# STLINK_V3EC.net
KiCad netlist of a schematic drawn in Altium Designer
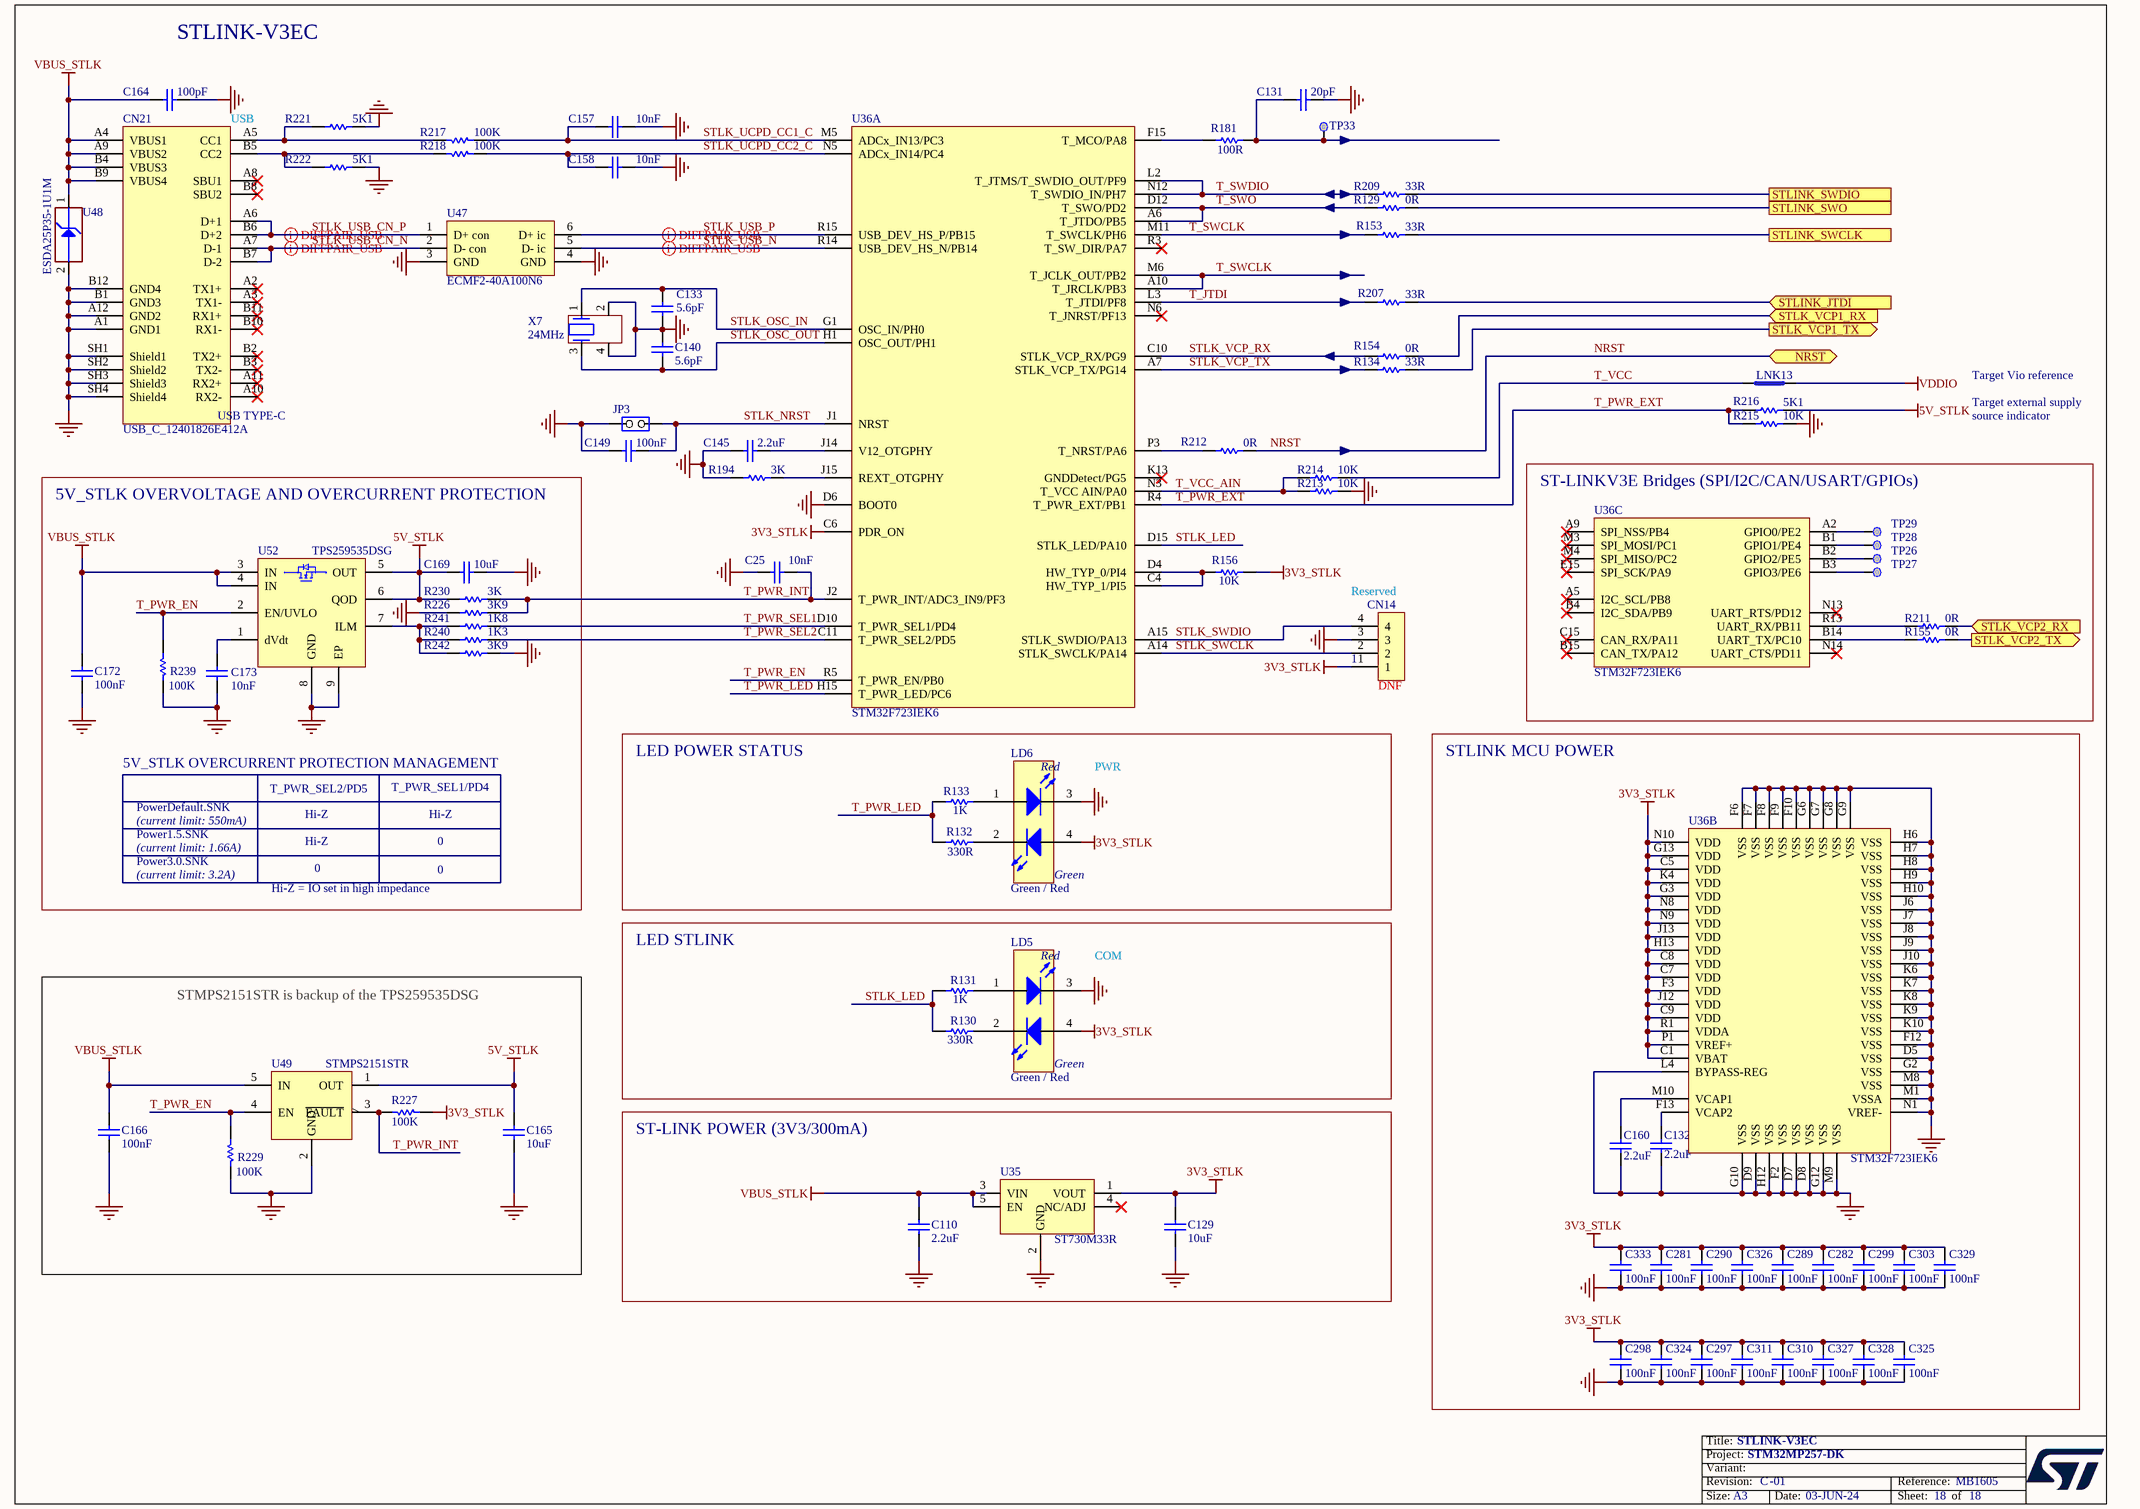
[diagram p0: STLINK_V3EC.SchDoc]

(export (version "E")
  (design (tool "Eeschema 10.0.6"))
  (components
    (comp (ref "C25")
      (value "10nF")
      (footprint "C0402")
      (description "Capacitor, MLCC, 10nF, 50V, X7R, +/-10%, 0402, T=0.5mm")
      (fields (field (name "INTERNAL_PART_NUMBER") "MCD-02198") (field (name "MANUFACTURER") "YAGEO"))
      (libsource (lib "MCD_PARTS_database") (part "Capacitor"))
    )
    (comp (ref "C110")
      (value "2.2uF")
      (footprint "C0805")
      (description "Capacitor, MLCC, 2.2uF, 25V, X7R, +/-10%, 0805, T=1,25mm")
      (fields
        (field (name "INTERNAL_PART_NUMBER") "MCD-02372")
        (field (name "MANUFACTURER_PART_NUMBER") "GRM21BR71E225KE11L")
      )
      (libsource (lib "MCD_PARTS_database") (part "Capacitor"))
    )
    (comp (ref "C129")
      (value "10uF")
      (footprint "C0603")
      (description "Capacitor, MLCC, 10uF, 10V, X5R, +/-10%, 0603, T=0.8mm")
      (fields (field (name "INTERNAL_PART_NUMBER") "MCD-00099") (field (name "MANUFACTURER") "MURATA"))
      (libsource (lib "MCD_PARTS_database") (part "Capacitor"))
    )
    (comp (ref "C131")
      (value "20pF")
      (footprint "C0402")
      (description "Capacitor, MLCC, 20pF, 50V, NPO, +/- 5%, 0402, T=0.5mm")
      (fields
        (field (name "INTERNAL_PART_NUMBER") "MCD-00016")
        (field (name "MANUFACTURER_PART_NUMBER") "CC0402JRNPO9BN200")
      )
      (libsource (lib "MCD_PARTS_database") (part "Capacitor"))
    )
    (comp (ref "C132")
      (value "2.2uF")
      (footprint "C0402")
      (description "Capacitor, MLCC, 2.2uF, 6.3V, X5R, +/-10%, 0402, T=0.5mm")
      (fields (field (name "INTERNAL_PART_NUMBER") "MCD-02606") (field (name "MANUFACTURER") "YAGEO"))
      (libsource (lib "MCD_PARTS_database") (part "Capacitor"))
    )
    (comp (ref "C133")
      (value "5.6pF")
      (footprint "C0402")
      (description "Capacitor, MLCC, 5.6pF, 50V, NPO, +/-0.1pF, 0402, T=0.5mm")
      (fields (field (name "INTERNAL_PART_NUMBER") "MCD-01374") (field (name "MANUFACTURER") "YAGEO"))
      (libsource (lib "MCD_PARTS_database") (part "Capacitor"))
    )
    (comp (ref "C140")
      (value "5.6pF")
      (footprint "C0402")
      (description "Capacitor, MLCC, 5.6pF, 50V, NPO, +/-0.1pF, 0402, T=0.5mm")
      (fields (field (name "INTERNAL_PART_NUMBER") "MCD-01374") (field (name "MANUFACTURER") "YAGEO"))
      (libsource (lib "MCD_PARTS_database") (part "Capacitor"))
    )
    (comp (ref "C145")
      (value "2.2uF")
      (footprint "C0402")
      (description "Capacitor, MLCC, 2.2uF, 6.3V, X5R, +/-10%, 0402, T=0.5mm")
      (fields (field (name "INTERNAL_PART_NUMBER") "MCD-02606") (field (name "MANUFACTURER") "YAGEO"))
      (libsource (lib "MCD_PARTS_database") (part "Capacitor"))
    )
    (comp (ref "C149")
      (value "100nF")
      (footprint "C0402")
      (description "Capacitor, MLCC, 100nF, 16V, X7R, +/-10%, 0402, T=0.5mm")
      (fields
        (field (name "INTERNAL_PART_NUMBER") "MCD-00006")
        (field (name "MANUFACTURER_PART_NUMBER") "CC0402KRX7R7BB104")
      )
      (libsource (lib "MCD_PARTS_database") (part "Capacitor"))
    )
    (comp (ref "C157")
      (value "10nF")
      (footprint "C0402")
      (description "Capacitor, MLCC, 10nF, 50V, X7R, +/-10%, 0402, T=0.5mm")
      (fields (field (name "INTERNAL_PART_NUMBER") "MCD-02198") (field (name "MANUFACTURER") "YAGEO"))
      (libsource (lib "MCD_PARTS_database") (part "Capacitor"))
    )
    (comp (ref "C158")
      (value "10nF")
      (footprint "C0402")
      (description "Capacitor, MLCC, 10nF, 50V, X7R, +/-10%, 0402, T=0.5mm")
      (fields (field (name "INTERNAL_PART_NUMBER") "MCD-02198") (field (name "MANUFACTURER") "YAGEO"))
      (libsource (lib "MCD_PARTS_database") (part "Capacitor"))
    )
    (comp (ref "C160")
      (value "2.2uF")
      (footprint "C0402")
      (description "Capacitor, MLCC, 2.2uF, 6.3V, X5R, +/-10%, 0402, T=0.5mm")
      (fields (field (name "INTERNAL_PART_NUMBER") "MCD-02606") (field (name "MANUFACTURER") "YAGEO"))
      (libsource (lib "MCD_PARTS_database") (part "Capacitor"))
    )
    (comp (ref "C164")
      (value "100pF")
      (footprint "C0402")
      (description "Capacitor, MLCC, 100pF, 50V, NPO, +/-5%, 0402, T=0.5mm")
      (fields (field (name "INTERNAL_PART_NUMBER") "MCD-00205") (field (name "MANUFACTURER") "YAGEO"))
      (libsource (lib "MCD_PARTS_database") (part "Capacitor"))
    )
    (comp (ref "C165")
      (value "10uF")
      (footprint "C0603")
      (description "Capacitor, MLCC, 10uF, 10V, X5R, +/-10%, 0603, T=0.8mm")
      (fields (field (name "INTERNAL_PART_NUMBER") "MCD-00099") (field (name "MANUFACTURER") "MURATA"))
      (libsource (lib "MCD_PARTS_database") (part "Capacitor"))
    )
    (comp (ref "C166")
      (value "100nF")
      (footprint "C0402")
      (description "Capacitor, MLCC, 100nF, 25V, X7R, +/-10%, 0402, T=0.5mm")
      (fields (field (name "INTERNAL_PART_NUMBER") "MCD-02355") (field (name "MANUFACTURER") "WALSIN"))
      (libsource (lib "MCD_PARTS_database") (part "Capacitor"))
    )
    (comp (ref "C169")
      (value "10uF")
      (footprint "C0603")
      (description "Capacitor, MLCC, 10uF, 10V, X5R, +/-10%, 0603, T=0.8mm")
      (fields (field (name "INTERNAL_PART_NUMBER") "MCD-00099") (field (name "MANUFACTURER") "MURATA"))
      (libsource (lib "MCD_PARTS_database") (part "Capacitor"))
    )
    (comp (ref "C172")
      (value "100nF")
      (footprint "C0402")
      (description "Capacitor, MLCC, 100nF, 25V, X7R, +/-10%, 0402, T=0.5mm")
      (fields (field (name "INTERNAL_PART_NUMBER") "MCD-02355") (field (name "MANUFACTURER") "WALSIN"))
      (libsource (lib "MCD_PARTS_database") (part "Capacitor"))
    )
    (comp (ref "C173")
      (value "10nF")
      (footprint "C0402")
      (description "Capacitor, MLCC, 10nF, 50V, X7R, +/-10%, 0402, T=0.5mm")
      (fields (field (name "INTERNAL_PART_NUMBER") "MCD-02198") (field (name "MANUFACTURER") "YAGEO"))
      (libsource (lib "MCD_PARTS_database") (part "Capacitor"))
    )
    (comp (ref "C281")
      (value "100nF")
      (footprint "C0402")
      (description "Capacitor, MLCC, 100nF, 16V, X7R, +/-10%, 0402, T=0.5mm")
      (fields
        (field (name "INTERNAL_PART_NUMBER") "MCD-00006")
        (field (name "MANUFACTURER_PART_NUMBER") "CC0402KRX7R7BB104")
      )
      (libsource (lib "MCD_PARTS_database") (part "Capacitor"))
    )
    (comp (ref "C282")
      (value "100nF")
      (footprint "C0402")
      (description "Capacitor, MLCC, 100nF, 16V, X7R, +/-10%, 0402, T=0.5mm")
      (fields
        (field (name "INTERNAL_PART_NUMBER") "MCD-00006")
        (field (name "MANUFACTURER_PART_NUMBER") "CC0402KRX7R7BB104")
      )
      (libsource (lib "MCD_PARTS_database") (part "Capacitor"))
    )
    (comp (ref "C289")
      (value "100nF")
      (footprint "C0402")
      (description "Capacitor, MLCC, 100nF, 16V, X7R, +/-10%, 0402, T=0.5mm")
      (fields
        (field (name "INTERNAL_PART_NUMBER") "MCD-00006")
        (field (name "MANUFACTURER_PART_NUMBER") "CC0402KRX7R7BB104")
      )
      (libsource (lib "MCD_PARTS_database") (part "Capacitor"))
    )
    (comp (ref "C290")
      (value "100nF")
      (footprint "C0402")
      (description "Capacitor, MLCC, 100nF, 16V, X7R, +/-10%, 0402, T=0.5mm")
      (fields
        (field (name "INTERNAL_PART_NUMBER") "MCD-00006")
        (field (name "MANUFACTURER_PART_NUMBER") "CC0402KRX7R7BB104")
      )
      (libsource (lib "MCD_PARTS_database") (part "Capacitor"))
    )
    (comp (ref "C297")
      (value "100nF")
      (footprint "C0402")
      (description "Capacitor, MLCC, 100nF, 16V, X7R, +/-10%, 0402, T=0.5mm")
      (fields
        (field (name "INTERNAL_PART_NUMBER") "MCD-00006")
        (field (name "MANUFACTURER_PART_NUMBER") "CC0402KRX7R7BB104")
      )
      (libsource (lib "MCD_PARTS_database") (part "Capacitor"))
    )
    (comp (ref "C298")
      (value "100nF")
      (footprint "C0402")
      (description "Capacitor, MLCC, 100nF, 16V, X7R, +/-10%, 0402, T=0.5mm")
      (fields
        (field (name "INTERNAL_PART_NUMBER") "MCD-00006")
        (field (name "MANUFACTURER_PART_NUMBER") "CC0402KRX7R7BB104")
      )
      (libsource (lib "MCD_PARTS_database") (part "Capacitor"))
    )
    (comp (ref "C299")
      (value "100nF")
      (footprint "C0402")
      (description "Capacitor, MLCC, 100nF, 16V, X7R, +/-10%, 0402, T=0.5mm")
      (fields
        (field (name "INTERNAL_PART_NUMBER") "MCD-00006")
        (field (name "MANUFACTURER_PART_NUMBER") "CC0402KRX7R7BB104")
      )
      (libsource (lib "MCD_PARTS_database") (part "Capacitor"))
    )
    (comp (ref "C303")
      (value "100nF")
      (footprint "C0402")
      (description "Capacitor, MLCC, 100nF, 16V, X7R, +/-10%, 0402, T=0.5mm")
      (fields
        (field (name "INTERNAL_PART_NUMBER") "MCD-00006")
        (field (name "MANUFACTURER_PART_NUMBER") "CC0402KRX7R7BB104")
      )
      (libsource (lib "MCD_PARTS_database") (part "Capacitor"))
    )
    (comp (ref "C310")
      (value "100nF")
      (footprint "C0402")
      (description "Capacitor, MLCC, 100nF, 16V, X7R, +/-10%, 0402, T=0.5mm")
      (fields
        (field (name "INTERNAL_PART_NUMBER") "MCD-00006")
        (field (name "MANUFACTURER_PART_NUMBER") "CC0402KRX7R7BB104")
      )
      (libsource (lib "MCD_PARTS_database") (part "Capacitor"))
    )
    (comp (ref "C311")
      (value "100nF")
      (footprint "C0402")
      (description "Capacitor, MLCC, 100nF, 16V, X7R, +/-10%, 0402, T=0.5mm")
      (fields
        (field (name "INTERNAL_PART_NUMBER") "MCD-00006")
        (field (name "MANUFACTURER_PART_NUMBER") "CC0402KRX7R7BB104")
      )
      (libsource (lib "MCD_PARTS_database") (part "Capacitor"))
    )
    (comp (ref "C324")
      (value "100nF")
      (footprint "C0402")
      (description "Capacitor, MLCC, 100nF, 16V, X7R, +/-10%, 0402, T=0.5mm")
      (fields
        (field (name "INTERNAL_PART_NUMBER") "MCD-00006")
        (field (name "MANUFACTURER_PART_NUMBER") "CC0402KRX7R7BB104")
      )
      (libsource (lib "MCD_PARTS_database") (part "Capacitor"))
    )
    (comp (ref "C325")
      (value "100nF")
      (footprint "C0402")
      (description "Capacitor, MLCC, 100nF, 16V, X7R, +/-10%, 0402, T=0.5mm")
      (fields
        (field (name "INTERNAL_PART_NUMBER") "MCD-00006")
        (field (name "MANUFACTURER_PART_NUMBER") "CC0402KRX7R7BB104")
      )
      (libsource (lib "MCD_PARTS_database") (part "Capacitor"))
    )
    (comp (ref "C326")
      (value "100nF")
      (footprint "C0402")
      (description "Capacitor, MLCC, 100nF, 16V, X7R, +/-10%, 0402, T=0.5mm")
      (fields
        (field (name "INTERNAL_PART_NUMBER") "MCD-00006")
        (field (name "MANUFACTURER_PART_NUMBER") "CC0402KRX7R7BB104")
      )
      (libsource (lib "MCD_PARTS_database") (part "Capacitor"))
    )
    (comp (ref "C327")
      (value "100nF")
      (footprint "C0402")
      (description "Capacitor, MLCC, 100nF, 16V, X7R, +/-10%, 0402, T=0.5mm")
      (fields
        (field (name "INTERNAL_PART_NUMBER") "MCD-00006")
        (field (name "MANUFACTURER_PART_NUMBER") "CC0402KRX7R7BB104")
      )
      (libsource (lib "MCD_PARTS_database") (part "Capacitor"))
    )
    (comp (ref "C328")
      (value "100nF")
      (footprint "C0402")
      (description "Capacitor, MLCC, 100nF, 16V, X7R, +/-10%, 0402, T=0.5mm")
      (fields
        (field (name "INTERNAL_PART_NUMBER") "MCD-00006")
        (field (name "MANUFACTURER_PART_NUMBER") "CC0402KRX7R7BB104")
      )
      (libsource (lib "MCD_PARTS_database") (part "Capacitor"))
    )
    (comp (ref "C329")
      (value "100nF")
      (footprint "C0402")
      (description "Capacitor, MLCC, 100nF, 16V, X7R, +/-10%, 0402, T=0.5mm")
      (fields
        (field (name "INTERNAL_PART_NUMBER") "MCD-00006")
        (field (name "MANUFACTURER_PART_NUMBER") "CC0402KRX7R7BB104")
      )
      (libsource (lib "MCD_PARTS_database") (part "Capacitor"))
    )
    (comp (ref "C333")
      (value "100nF")
      (footprint "C0402")
      (description "Capacitor, MLCC, 100nF, 16V, X7R, +/-10%, 0402, T=0.5mm")
      (fields
        (field (name "INTERNAL_PART_NUMBER") "MCD-00006")
        (field (name "MANUFACTURER_PART_NUMBER") "CC0402KRX7R7BB104")
      )
      (libsource (lib "MCD_PARTS_database") (part "Capacitor"))
    )
    (comp (ref "CN14")
      (value "Header 4x1")
      (footprint "CON_SAMTEC_TSW-104-07-G-S")
      (description "Header, 4x1, 2.54mm, VR, TH, T=5.84mm/2.54mm")
      (fields
        (field (name "INTERNAL_PART_NUMBER") "MCD-00029")
        (field (name "MANUFACTURER_PART_NUMBER") "TSW-104-07-G-S")
      )
      (libsource (lib "MCD_PARTS_database") (part "Header 4x1"))
    )
    (comp (ref "CN21")
      (value "USB_C_12401826E412A")
      (footprint "CON_USB-TYPEC_AMPHENOL_12401826E412A")
      (description "USB_TypeC, 24 pins, RA, SMD, T=2.96mm (USB Certified 3.1)")
      (fields (field (name "INTERNAL_PART_NUMBER") "MCD-03232") (field (name "MANUFACTURER") "AMPHENOL ICC"))
      (libsource (lib "MCD_PARTS_database") (part "USB_TYPE_C_Receptacle"))
    )
    (comp (ref "JP3")
      (value "Jumper_Header 2x1")
      (footprint "CON_SAMTEC_TSW-102-07-G-S")
      (description "Header, 2x1, 2.54mm, VR, TH, T=5.84mm/2.54mm")
      (fields (field (name "INTERNAL_PART_NUMBER") "MCD-00045") (field (name "MANUFACTURER") "SAMTEC"))
      (libsource (lib "MCD_PARTS_database") (part "Jumper_Header 2x1"))
    )
    (comp (ref "LD5")
      (value "Green / Red")
      (footprint "LED_BI-GR_WE-150141SV73110")
      (description "LED Bicolor, Green/Red, 2V, 20mA,  4-PLCC")
      (fields
        (field (name "INTERNAL_PART_NUMBER") "MCD-02631")
        (field (name "MANUFACTURER") "WURTH ELEKTRONIK")
      )
      (libsource (lib "MCD_PARTS_database") (part "LED_BICOLOR"))
    )
    (comp (ref "LD6")
      (value "Green / Red")
      (footprint "LED_BI-GR_WE-150141SV73110")
      (description "LED Bicolor, Green/Red, 2V, 20mA,  4-PLCC")
      (fields
        (field (name "INTERNAL_PART_NUMBER") "MCD-02631")
        (field (name "MANUFACTURER") "WURTH ELEKTRONIK")
      )
      (libsource (lib "MCD_PARTS_database") (part "LED_BICOLOR"))
    )
    (comp (ref "LNK13")
      (value "link_200")
      (footprint "LINK200")
      (description "Track link on PCB 200um width for layout routing. No component assembly and no component in BOM")
      (fields (field (name "INTERNAL_PART_NUMBER") "MCD-02777"))
      (libsource (lib "MCD_PARTS_database") (part "link_200"))
    )
    (comp (ref "R129")
      (value "0R")
      (footprint "R0402")
      (description "Resistor, 0R, 0402, +/-5%, 1/16W")
      (fields (field (name "INTERNAL_PART_NUMBER") "MCD-00052") (field (name "MANUFACTURER") "YAGEO"))
      (libsource (lib "MCD_PARTS_database") (part "Resistor"))
    )
    (comp (ref "R130")
      (value "330R")
      (footprint "R0402")
      (description "Resistor, 330R, 0402, +/-1%, 1/16W")
      (fields (field (name "INTERNAL_PART_NUMBER") "MCD-00062") (field (name "MANUFACTURER") "YAGEO"))
      (libsource (lib "MCD_PARTS_database") (part "Resistor"))
    )
    (comp (ref "R131")
      (value "1K")
      (footprint "R0402")
      (description "Resistor, 1K, 0402, +/-0.1%, 1/16W, +/-25ppm/°C")
      (fields (field (name "INTERNAL_PART_NUMBER") "MCD-02665") (field (name "MANUFACTURER") "YAGEO"))
      (libsource (lib "MCD_PARTS_database") (part "Resistor"))
    )
    (comp (ref "R132")
      (value "330R")
      (footprint "R0402")
      (description "Resistor, 330R, 0402, +/-1%, 1/16W")
      (fields (field (name "INTERNAL_PART_NUMBER") "MCD-00062") (field (name "MANUFACTURER") "YAGEO"))
      (libsource (lib "MCD_PARTS_database") (part "Resistor"))
    )
    (comp (ref "R133")
      (value "1K")
      (footprint "R0402")
      (description "Resistor, 1K, 0402, +/-0.1%, 1/16W, +/-25ppm/°C")
      (fields (field (name "INTERNAL_PART_NUMBER") "MCD-02665") (field (name "MANUFACTURER") "YAGEO"))
      (libsource (lib "MCD_PARTS_database") (part "Resistor"))
    )
    (comp (ref "R134")
      (value "33R")
      (footprint "R0402")
      (description "Resistor, 33R, 0402, +/-1%, 1/16W")
      (fields (field (name "INTERNAL_PART_NUMBER") "MCD-00455") (field (name "MANUFACTURER") "YAGEO"))
      (libsource (lib "MCD_PARTS_database") (part "Resistor"))
    )
    (comp (ref "R153")
      (value "33R")
      (footprint "R0402")
      (description "Resistor, 33R, 0402, +/-1%, 1/16W")
      (fields (field (name "INTERNAL_PART_NUMBER") "MCD-00455") (field (name "MANUFACTURER") "YAGEO"))
      (libsource (lib "MCD_PARTS_database") (part "Resistor"))
    )
    (comp (ref "R154")
      (value "0R")
      (footprint "R0402")
      (description "Resistor, 0R, 0402, +/-5%, 1/16W")
      (fields (field (name "INTERNAL_PART_NUMBER") "MCD-00052") (field (name "MANUFACTURER") "YAGEO"))
      (libsource (lib "MCD_PARTS_database") (part "Resistor"))
    )
    (comp (ref "R155")
      (value "0R")
      (footprint "R0402")
      (description "Resistor, 0R, 0402, +/-5%, 1/16W")
      (fields
        (field (name "INTERNAL_PART_NUMBER") "MCD-00052")
        (field (name "MANUFACTURER_PART_NUMBER") "RC0402JR-070RL")
      )
      (libsource (lib "MCD_PARTS_database") (part "Resistor"))
    )
    (comp (ref "R156")
      (value "10K")
      (footprint "R0402")
      (description "Resistor, 10K, 0402, +/-1%, 1/16W")
      (fields
        (field (name "INTERNAL_PART_NUMBER") "MCD-00053")
        (field (name "MANUFACTURER_PART_NUMBER") "RC0402FR-0710KL")
      )
      (libsource (lib "MCD_PARTS_database") (part "Resistor"))
    )
    (comp (ref "R181")
      (value "100R")
      (footprint "R0402")
      (description "Resistor, 100R, 0402, +/- 1%, 1/16W")
      (fields (field (name "INTERNAL_PART_NUMBER") "MCD-00067") (field (name "MANUFACTURER") "YAGEO"))
      (libsource (lib "MCD_PARTS_database") (part "Resistor"))
    )
    (comp (ref "R194")
      (value "3K")
      (footprint "R0402")
      (description "Resistor, 3K, 0402, +/-1%, 1/16W")
      (fields
        (field (name "INTERNAL_PART_NUMBER") "MCD-00185")
        (field (name "MANUFACTURER_PART_NUMBER") "RC0402FR-073KL")
      )
      (libsource (lib "MCD_PARTS_database") (part "Resistor"))
    )
    (comp (ref "R207")
      (value "33R")
      (footprint "R0402")
      (description "Resistor, 33R, 0402, +/-1%, 1/16W")
      (fields (field (name "INTERNAL_PART_NUMBER") "MCD-00455") (field (name "MANUFACTURER") "YAGEO"))
      (libsource (lib "MCD_PARTS_database") (part "Resistor"))
    )
    (comp (ref "R209")
      (value "33R")
      (footprint "R0402")
      (description "Resistor, 33R, 0402, +/-1%, 1/16W")
      (fields (field (name "INTERNAL_PART_NUMBER") "MCD-00455") (field (name "MANUFACTURER") "YAGEO"))
      (libsource (lib "MCD_PARTS_database") (part "Resistor"))
    )
    (comp (ref "R211")
      (value "0R")
      (footprint "R0402")
      (description "Resistor, 0R, 0402, +/-5%, 1/16W")
      (fields
        (field (name "INTERNAL_PART_NUMBER") "MCD-00052")
        (field (name "MANUFACTURER_PART_NUMBER") "RC0402JR-070RL")
      )
      (libsource (lib "MCD_PARTS_database") (part "Resistor"))
    )
    (comp (ref "R212")
      (value "0R")
      (footprint "R0402")
      (description "Resistor, 0R, 0402, +/-5%, 1/16W")
      (fields (field (name "INTERNAL_PART_NUMBER") "MCD-00052") (field (name "MANUFACTURER") "YAGEO"))
      (libsource (lib "MCD_PARTS_database") (part "Resistor"))
    )
    (comp (ref "R213")
      (value "10K")
      (footprint "R0402")
      (description "Resistor, 10K, 0402, +/-1%, 1/16W")
      (fields
        (field (name "INTERNAL_PART_NUMBER") "MCD-00053")
        (field (name "MANUFACTURER_PART_NUMBER") "RC0402FR-0710KL")
      )
      (libsource (lib "MCD_PARTS_database") (part "Resistor"))
    )
    (comp (ref "R214")
      (value "10K")
      (footprint "R0402")
      (description "Resistor, 10K, 0402, +/-1%, 1/16W")
      (fields
        (field (name "INTERNAL_PART_NUMBER") "MCD-00053")
        (field (name "MANUFACTURER_PART_NUMBER") "RC0402FR-0710KL")
      )
      (libsource (lib "MCD_PARTS_database") (part "Resistor"))
    )
    (comp (ref "R215")
      (value "10K")
      (footprint "R0402")
      (description "Resistor, 10K, 0402, +/-1%, 1/16W")
      (fields
        (field (name "INTERNAL_PART_NUMBER") "MCD-00053")
        (field (name "MANUFACTURER_PART_NUMBER") "RC0402FR-0710KL")
      )
      (libsource (lib "MCD_PARTS_database") (part "Resistor"))
    )
    (comp (ref "R216")
      (value "5K1")
      (footprint "R0402")
      (description "Resistor, 5K1, 0402, +/-1%, 1/16W")
      (fields (field (name "INTERNAL_PART_NUMBER") "MCD-00333") (field (name "MANUFACTURER") "YAGEO"))
      (libsource (lib "MCD_PARTS_database") (part "Resistor"))
    )
    (comp (ref "R217")
      (value "100K")
      (footprint "R0402")
      (description "Resistor, 100K, 0402, +/-1%, 1/16W")
      (fields
        (field (name "INTERNAL_PART_NUMBER") "MCD-00059")
        (field (name "MANUFACTURER_PART_NUMBER") "RC0402FR-07100KL")
      )
      (libsource (lib "MCD_PARTS_database") (part "Resistor"))
    )
    (comp (ref "R218")
      (value "100K")
      (footprint "R0402")
      (description "Resistor, 100K, 0402, +/-1%, 1/16W")
      (fields
        (field (name "INTERNAL_PART_NUMBER") "MCD-00059")
        (field (name "MANUFACTURER_PART_NUMBER") "RC0402FR-07100KL")
      )
      (libsource (lib "MCD_PARTS_database") (part "Resistor"))
    )
    (comp (ref "R221")
      (value "5K1")
      (footprint "R0402")
      (description "Resistor, 5K1, 0402, +/-1%, 1/16W")
      (fields (field (name "INTERNAL_PART_NUMBER") "MCD-00333") (field (name "MANUFACTURER") "YAGEO"))
      (libsource (lib "MCD_PARTS_database") (part "Resistor"))
    )
    (comp (ref "R222")
      (value "5K1")
      (footprint "R0402")
      (description "Resistor, 5K1, 0402, +/-1%, 1/16W")
      (fields (field (name "INTERNAL_PART_NUMBER") "MCD-00333") (field (name "MANUFACTURER") "YAGEO"))
      (libsource (lib "MCD_PARTS_database") (part "Resistor"))
    )
    (comp (ref "R226")
      (value "3K9")
      (footprint "R0402")
      (description "Resistor, 3K9, 0402, +/-1%, 1/16W, +/-100ppm/°C")
      (fields (field (name "INTERNAL_PART_NUMBER") "MCD-02455") (field (name "MANUFACTURER") "YAGEO"))
      (libsource (lib "MCD_PARTS_database") (part "Resistor"))
    )
    (comp (ref "R227")
      (value "100K")
      (footprint "R0402")
      (description "Resistor, 100K, 0402, +/-1%, 1/16W")
      (fields
        (field (name "INTERNAL_PART_NUMBER") "MCD-00059")
        (field (name "MANUFACTURER_PART_NUMBER") "RC0402FR-07100KL")
      )
      (libsource (lib "MCD_PARTS_database") (part "Resistor"))
    )
    (comp (ref "R229")
      (value "100K")
      (footprint "R0402")
      (description "Resistor, 100K, 0402, +/-1%, 1/16W")
      (fields
        (field (name "INTERNAL_PART_NUMBER") "MCD-00059")
        (field (name "MANUFACTURER_PART_NUMBER") "RC0402FR-07100KL")
      )
      (libsource (lib "MCD_PARTS_database") (part "Resistor"))
    )
    (comp (ref "R230")
      (value "3K")
      (footprint "R0402")
      (description "Resistor, 3K, 0402, +/-1%, 1/16W")
      (fields (field (name "INTERNAL_PART_NUMBER") "MCD-00185") (field (name "MANUFACTURER") "YAGEO"))
      (libsource (lib "MCD_PARTS_database") (part "Resistor"))
    )
    (comp (ref "R239")
      (value "100K")
      (footprint "R0402")
      (description "Resistor, 100K, 0402, +/-1%, 1/16W")
      (fields
        (field (name "INTERNAL_PART_NUMBER") "MCD-00059")
        (field (name "MANUFACTURER_PART_NUMBER") "RC0402FR-07100KL")
      )
      (libsource (lib "MCD_PARTS_database") (part "Resistor"))
    )
    (comp (ref "R240")
      (value "1K3")
      (footprint "R0402")
      (description "Resistor, 1K3, 0402, +/-1%, 1/16W")
      (fields (field (name "INTERNAL_PART_NUMBER") "MCD-00381") (field (name "MANUFACTURER") "YAGEO"))
      (libsource (lib "MCD_PARTS_database") (part "Resistor"))
    )
    (comp (ref "R241")
      (value "1K8")
      (footprint "R0402")
      (description "Resistor, 1K8, 0402, +/-1%, 1/16W")
      (fields (field (name "INTERNAL_PART_NUMBER") "MCD-00409") (field (name "MANUFACTURER") "YAGEO"))
      (libsource (lib "MCD_PARTS_database") (part "Resistor"))
    )
    (comp (ref "R242")
      (value "3K9")
      (footprint "R0402")
      (description "Resistor, 3K9, 0402, +/-1%, 1/16W, +/-100ppm/°C")
      (fields (field (name "INTERNAL_PART_NUMBER") "MCD-02455") (field (name "MANUFACTURER") "YAGEO"))
      (libsource (lib "MCD_PARTS_database") (part "Resistor"))
    )
    (comp (ref "TP26")
      (value "Test Point")
      (footprint "TP_SMD_1MM")
      (description "Test Point 1mm")
      (fields
        (field (name "INTERNAL_PART_NUMBER") "MCD-00074")
        (field (name "MANUFACTURER_PART_NUMBER") "n/a")
      )
      (libsource (lib "MCD_PARTS_database") (part "Test Point"))
    )
    (comp (ref "TP27")
      (value "Test Point")
      (footprint "TP_SMD_1MM")
      (description "Test Point 1mm")
      (fields
        (field (name "INTERNAL_PART_NUMBER") "MCD-00074")
        (field (name "MANUFACTURER_PART_NUMBER") "n/a")
      )
      (libsource (lib "MCD_PARTS_database") (part "Test Point"))
    )
    (comp (ref "TP28")
      (value "Test Point")
      (footprint "TP_SMD_1MM")
      (description "Test Point 1mm")
      (fields
        (field (name "INTERNAL_PART_NUMBER") "MCD-00074")
        (field (name "MANUFACTURER_PART_NUMBER") "n/a")
      )
      (libsource (lib "MCD_PARTS_database") (part "Test Point"))
    )
    (comp (ref "TP29")
      (value "Test Point")
      (footprint "TP_SMD_1MM")
      (description "Test Point 1mm")
      (fields
        (field (name "INTERNAL_PART_NUMBER") "MCD-00074")
        (field (name "MANUFACTURER_PART_NUMBER") "n/a")
      )
      (libsource (lib "MCD_PARTS_database") (part "Test Point"))
    )
    (comp (ref "TP33")
      (value "Test Point")
      (footprint "TP_SMD_1MM")
      (description "Test Point 1mm")
      (fields (field (name "INTERNAL_PART_NUMBER") "MCD-00074"))
      (libsource (lib "") (part "Test Point_1"))
    )
    (comp (ref "U35")
      (value "ST730M33R")
      (footprint "ICC_SOT23-5L_H1P45")
      (description "LDO, 3.3V, 300mA, High input voltage: 2.5V to 28V, SOT23-5L")
      (fields
        (field (name "INTERNAL_PART_NUMBER") "MCD-02514")
        (field (name "MANUFACTURER") "STMICROELECTRONICS")
      )
      (libsource (lib "MCD_PARTS_database") (part "ST730M33R"))
    )
    (comp (ref "U36")
      (value "STM32F723IEK6")
      (footprint "ICC_UFBGA201_176+25_10X10_P065")
      (description "MCU, ARM Cortex-M7 32-bit, 512KB Flash, 276KB RAM, With Crypto")
      (fields
        (field (name "INTERNAL_PART_NUMBER") "MCD-03851")
        (field (name "MANUFACTURER") "STMICROELECTRONICS")
      )
      (libsource (lib "MCD_PARTS_database") (part "STLINK-V3EC"))
    )
    (comp (ref "U47")
      (value "ECMF2-40A100N6")
      (footprint "ESD_UQFN-6L_1P45X1P4_P040")
      (description "IC, ESD protection and Common Filter High Speed serial Interfaces, 10.7 GHz")
      (fields
        (field (name "INTERNAL_PART_NUMBER") "MCD-03060")
        (field (name "MANUFACTURER") "STMICROELECTRONICS")
      )
      (libsource (lib "MCD_PARTS_database") (part "ECMF2-40A100N6"))
    )
    (comp (ref "U48")
      (value "ESDA25P35-1U1M")
      (footprint "ESD_QFN1610_2N_1K_2A")
      (description "High power Transient voltage suppressor:25V/35A EOS and ESD transients protection.")
      (fields
        (field (name "INTERNAL_PART_NUMBER") "MCD-01207")
        (field (name "MANUFACTURER") "STMICROELECTRONICS")
      )
      (libsource (lib "MCD_PARTS_database") (part "ESD-TRANSIL"))
    )
    (comp (ref "U49")
      (value "STMPS2151STR")
      (footprint "MOS_SOT23-5L")
      (description "500mA, Enhanced single channel power switches with active high enable pin")
      (fields
        (field (name "INTERNAL_PART_NUMBER") "MCD-00159")
        (field (name "MANUFACTURER") "STMICROELECTRONICS")
        (field (name "PROVIDED_BY") "Subcon")
      )
      (libsource (lib "MCD_PARTS_database") (part "STMPS2151STR"))
    )
    (comp (ref "U52")
      (value "TPS259535DSG")
      (footprint "ICC_WSON8-EPAD_2X2_P050")
      (description "IC, eFuse with Fast Overvoltage Protection 2.7V to 18V 4A 34mOhm 8-Pin WSON")
      (fields
        (field (name "INTERNAL_PART_NUMBER") "MCD-02532")
        (field (name "MANUFACTURER") "TEXAS INSTRUMENTS")
      )
      (libsource (lib "MCD_PARTS_database") (part "TPS259535DSG"))
    )
    (comp (ref "X7")
      (value "24MHz")
      (footprint "CRY_NX2016SA_4P")
      (description "Crystal, 24MHz, 6pF, +/-20ppm, 80R, 2x1.6mm")
      (fields (field (name "INTERNAL_PART_NUMBER") "MCD-01036") (field (name "BMS_PART_NUMBER") "9157045"))
      (libsource (lib "MCD_PARTS_database") (part "XTAL_4_PINS"))
    )
  )
  (nets
    (net (code "1") (name "/NRST") (class "Default")
      (node (ref "R212") (pin "2") (pinfunction "2_2") (pintype "passive"))
    )
    (net (code "2") (name "/STLINK_JTDI") (class "Default")
      (node (ref "R207") (pin "2") (pinfunction "2_2") (pintype "passive"))
    )
    (net (code "3") (name "/STLINK_SWCLK") (class "Default")
      (node (ref "R153") (pin "2") (pinfunction "2_2") (pintype "passive"))
    )
    (net (code "4") (name "/STLINK_SWDIO") (class "Default")
      (node (ref "R209") (pin "2") (pinfunction "2_2") (pintype "passive"))
    )
    (net (code "5") (name "/STLINK_SWO") (class "Default")
      (node (ref "R129") (pin "2") (pinfunction "2_2") (pintype "passive"))
    )
    (net (code "6") (name "/STLK_LED") (class "Default")
      (node (ref "R130") (pin "1") (pinfunction "1_1") (pintype "passive"))
      (node (ref "R131") (pin "2") (pinfunction "2_2") (pintype "passive"))
      (node (ref "U36") (pin "D15") (pinfunction "STLK_LED/PA10_D15") (pintype "passive"))
    )
    (net (code "7") (name "/STLK_NRST") (class "Default")
      (node (ref "C149") (pin "2") (pinfunction "2_2") (pintype "passive"))
      (node (ref "JP3") (pin "1") (pinfunction "COMMON_1") (pintype "passive"))
      (node (ref "U36") (pin "J1") (pinfunction "NRST_J1") (pintype "passive"))
    )
    (net (code "8") (name "/STLK_OSC_IN") (class "Default")
      (node (ref "C133") (pin "2") (pinfunction "2_2") (pintype "passive"))
      (node (ref "U36") (pin "G1") (pinfunction "OSC_IN/PH0_G1") (pintype "passive"))
      (node (ref "X7") (pin "1") (pinfunction "1_1") (pintype "passive"))
    )
    (net (code "9") (name "/STLK_OSC_OUT") (class "Default")
      (node (ref "C140") (pin "1") (pinfunction "1_1") (pintype "passive"))
      (node (ref "U36") (pin "H1") (pinfunction "OSC_OUT/PH1_H1") (pintype "passive"))
      (node (ref "X7") (pin "3") (pinfunction "3_3") (pintype "passive"))
    )
    (net (code "10") (name "/STLK_SWCLK") (class "Default")
      (node (ref "CN14") (pin "2") (pinfunction "2_2") (pintype "passive"))
      (node (ref "U36") (pin "A14") (pinfunction "STLK_SWCLK/PA14_A14") (pintype "passive"))
    )
    (net (code "11") (name "/STLK_SWDIO") (class "Default")
      (node (ref "CN14") (pin "4") (pinfunction "4_4") (pintype "passive"))
      (node (ref "U36") (pin "A15") (pinfunction "STLK_SWDIO/PA13_A15") (pintype "passive"))
    )
    (net (code "12") (name "/STLK_UCPD_CC1_C") (class "Default")
      (node (ref "C157") (pin "1") (pinfunction "1_1") (pintype "passive"))
      (node (ref "R217") (pin "1") (pinfunction "1_1") (pintype "passive"))
      (node (ref "U36") (pin "M5") (pinfunction "ADCx_IN13/PC3_M5") (pintype "passive"))
    )
    (net (code "13") (name "/STLK_UCPD_CC2_C") (class "Default")
      (node (ref "C158") (pin "1") (pinfunction "1_1") (pintype "passive"))
      (node (ref "R218") (pin "1") (pinfunction "1_1") (pintype "passive"))
      (node (ref "U36") (pin "N5") (pinfunction "ADCx_IN14/PC4_N5") (pintype "passive"))
    )
    (net (code "14") (name "/STLK_USB_CN_N") (class "Default")
      (node (ref "CN21") (pin "A7") (pinfunction "D-1_A7") (pintype "passive"))
      (node (ref "CN21") (pin "B7") (pinfunction "D-2_B7") (pintype "passive"))
      (node (ref "U47") (pin "2") (pinfunction "D-_con_2") (pintype "passive"))
    )
    (net (code "15") (name "/STLK_USB_CN_P") (class "Default")
      (node (ref "CN21") (pin "A6") (pinfunction "D+1_A6") (pintype "passive"))
      (node (ref "CN21") (pin "B6") (pinfunction "D+2_B6") (pintype "passive"))
      (node (ref "U47") (pin "1") (pinfunction "D+_con_1") (pintype "passive"))
    )
    (net (code "16") (name "/STLK_USB_N") (class "Default")
      (node (ref "U36") (pin "R14") (pinfunction "USB_DEV_HS_N/PB14_R14") (pintype "passive"))
      (node (ref "U47") (pin "5") (pinfunction "D-_ic_5") (pintype "passive"))
    )
    (net (code "17") (name "/STLK_USB_P") (class "Default")
      (node (ref "U36") (pin "R15") (pinfunction "USB_DEV_HS_P/PB15_R15") (pintype "passive"))
      (node (ref "U47") (pin "6") (pinfunction "D+_ic_6") (pintype "passive"))
    )
    (net (code "18") (name "/STLK_VCP1_RX") (class "Default")
      (node (ref "R154") (pin "2") (pinfunction "2_2") (pintype "passive"))
    )
    (net (code "19") (name "/STLK_VCP1_TX") (class "Default")
      (node (ref "R134") (pin "2") (pinfunction "2_2") (pintype "passive"))
    )
    (net (code "20") (name "/STLK_VCP2_RX") (class "Default")
      (node (ref "R211") (pin "1") (pinfunction "1_1") (pintype "passive"))
    )
    (net (code "21") (name "/STLK_VCP2_TX") (class "Default")
      (node (ref "R155") (pin "1") (pinfunction "1_1") (pintype "passive"))
    )
    (net (code "22") (name "/STLK_VCP_RX") (class "Default")
      (node (ref "R154") (pin "1") (pinfunction "1_1") (pintype "passive"))
      (node (ref "U36") (pin "C10") (pinfunction "STLK_VCP_RX/PG9_C10") (pintype "passive"))
    )
    (net (code "23") (name "/STLK_VCP_TX") (class "Default")
      (node (ref "R134") (pin "1") (pinfunction "1_1") (pintype "passive"))
      (node (ref "U36") (pin "A7") (pinfunction "STLK_VCP_TX/PG14_A7") (pintype "passive"))
    )
    (net (code "24") (name "/T_JTDI") (class "Default")
      (node (ref "R207") (pin "1") (pinfunction "1_1") (pintype "passive"))
      (node (ref "U36") (pin "L3") (pinfunction "T_JTDI/PF8_L3") (pintype "passive"))
    )
    (net (code "25") (name "/T_PWR_EN") (class "Default")
      (node (ref "R229") (pin "2") (pinfunction "2_2") (pintype "passive"))
      (node (ref "R239") (pin "2") (pinfunction "2_2") (pintype "passive"))
      (node (ref "U36") (pin "R5") (pinfunction "T_PWR_EN/PB0_R5") (pintype "passive"))
      (node (ref "U49") (pin "4") (pinfunction "EN_4") (pintype "passive"))
      (node (ref "U52") (pin "2") (pinfunction "EN/UVLO_2") (pintype "passive"))
    )
    (net (code "26") (name "/T_PWR_EXT") (class "Default")
      (node (ref "R215") (pin "1") (pinfunction "1_1") (pintype "passive"))
      (node (ref "R216") (pin "1") (pinfunction "1_1") (pintype "passive"))
      (node (ref "U36") (pin "R4") (pinfunction "T_PWR_EXT/PB1_R4") (pintype "passive"))
    )
    (net (code "27") (name "/T_PWR_INT") (class "Default")
      (node (ref "C25") (pin "2") (pinfunction "2_2") (pintype "passive"))
      (node (ref "R226") (pin "2") (pinfunction "2_2") (pintype "passive"))
      (node (ref "R227") (pin "2") (pinfunction "2_2") (pintype "passive"))
      (node (ref "R230") (pin "2") (pinfunction "2_2") (pintype "passive"))
      (node (ref "U36") (pin "J2") (pinfunction "T_PWR_INT/ADC3_IN9/PF3_J2") (pintype "passive"))
      (node (ref "U49") (pin "3") (pinfunction "~{FAULT}_3") (pintype "passive"))
    )
    (net (code "28") (name "/T_PWR_LED") (class "Default")
      (node (ref "R132") (pin "2") (pinfunction "2_2") (pintype "passive"))
      (node (ref "R133") (pin "2") (pinfunction "2_2") (pintype "passive"))
      (node (ref "U36") (pin "H15") (pinfunction "T_PWR_LED/PC6_H15") (pintype "passive"))
    )
    (net (code "29") (name "/T_PWR_SEL1") (class "Default")
      (node (ref "R241") (pin "2") (pinfunction "2_2") (pintype "passive"))
      (node (ref "U36") (pin "D10") (pinfunction "T_PWR_SEL1/PD4_D10") (pintype "passive"))
    )
    (net (code "30") (name "/T_PWR_SEL2") (class "Default")
      (node (ref "R240") (pin "2") (pinfunction "2_2") (pintype "passive"))
      (node (ref "U36") (pin "C11") (pinfunction "T_PWR_SEL2/PD5_C11") (pintype "passive"))
    )
    (net (code "31") (name "/T_SWCLK") (class "Default")
      (node (ref "R153") (pin "1") (pinfunction "1_1") (pintype "passive"))
      (node (ref "U36") (pin "A10") (pinfunction "T_JRCLK/PB3_A10") (pintype "passive"))
      (node (ref "U36") (pin "M11") (pinfunction "T_SWCLK/PH6_M11") (pintype "passive"))
      (node (ref "U36") (pin "M6") (pinfunction "T_JCLK_OUT/PB2_M6") (pintype "passive"))
    )
    (net (code "32") (name "/T_SWDIO") (class "Default")
      (node (ref "R209") (pin "1") (pinfunction "1_1") (pintype "passive"))
      (node (ref "U36") (pin "L2") (pinfunction "T_JTMS/T_SWDIO_OUT/PF9_L2") (pintype "passive"))
      (node (ref "U36") (pin "N12") (pinfunction "T_SWDIO_IN/PH7_N12") (pintype "passive"))
    )
    (net (code "33") (name "/T_SWO") (class "Default")
      (node (ref "R129") (pin "1") (pinfunction "1_1") (pintype "passive"))
      (node (ref "U36") (pin "A6") (pinfunction "T_JTDO/PB5_A6") (pintype "passive"))
      (node (ref "U36") (pin "D12") (pinfunction "T_SWO/PD2_D12") (pintype "passive"))
    )
    (net (code "34") (name "/T_VCC") (class "Default")
      (node (ref "LNK13") (pin "2") (pinfunction "2_2") (pintype "passive"))
      (node (ref "R214") (pin "2") (pinfunction "2_2") (pintype "passive"))
    )
    (net (code "35") (name "/T_VCC_AIN") (class "Default")
      (node (ref "R213") (pin "1") (pinfunction "1_1") (pintype "passive"))
      (node (ref "R214") (pin "1") (pinfunction "1_1") (pintype "passive"))
      (node (ref "U36") (pin "N3") (pinfunction "T_VCC_AIN/PA0_N3") (pintype "passive"))
    )
    (net (code "36") (name "3V3_STLK") (class "Default")
      (node (ref "C129") (pin "2") (pinfunction "2_2") (pintype "passive"))
      (node (ref "C281") (pin "1") (pinfunction "1_1") (pintype "passive"))
      (node (ref "C282") (pin "1") (pinfunction "1_1") (pintype "passive"))
      (node (ref "C289") (pin "1") (pinfunction "1_1") (pintype "passive"))
      (node (ref "C290") (pin "1") (pinfunction "1_1") (pintype "passive"))
      (node (ref "C297") (pin "1") (pinfunction "1_1") (pintype "passive"))
      (node (ref "C298") (pin "1") (pinfunction "1_1") (pintype "passive"))
      (node (ref "C299") (pin "1") (pinfunction "1_1") (pintype "passive"))
      (node (ref "C303") (pin "1") (pinfunction "1_1") (pintype "passive"))
      (node (ref "C310") (pin "1") (pinfunction "1_1") (pintype "passive"))
      (node (ref "C311") (pin "1") (pinfunction "1_1") (pintype "passive"))
      (node (ref "C324") (pin "1") (pinfunction "1_1") (pintype "passive"))
      (node (ref "C325") (pin "1") (pinfunction "1_1") (pintype "passive"))
      (node (ref "C326") (pin "1") (pinfunction "1_1") (pintype "passive"))
      (node (ref "C327") (pin "1") (pinfunction "1_1") (pintype "passive"))
      (node (ref "C328") (pin "1") (pinfunction "1_1") (pintype "passive"))
      (node (ref "C329") (pin "1") (pinfunction "1_1") (pintype "passive"))
      (node (ref "C333") (pin "1") (pinfunction "1_1") (pintype "passive"))
      (node (ref "CN14") (pin "1") (pinfunction "1_1") (pintype "passive"))
      (node (ref "LD5") (pin "4") (pinfunction "Green_anode_4") (pintype "passive"))
      (node (ref "LD6") (pin "4") (pinfunction "Green_anode_4") (pintype "passive"))
      (node (ref "R156") (pin "2") (pinfunction "2_2") (pintype "passive"))
      (node (ref "R227") (pin "1") (pinfunction "1_1") (pintype "passive"))
      (node (ref "U35") (pin "1") (pinfunction "VOUT_1") (pintype "passive"))
      (node (ref "U36") (pin "C1") (pinfunction "VBAT_C1") (pintype "passive"))
      (node (ref "U36") (pin "C5") (pinfunction "VDD_C5") (pintype "passive"))
      (node (ref "U36") (pin "C6") (pinfunction "PDR_ON_C6") (pintype "passive"))
      (node (ref "U36") (pin "C7") (pinfunction "VDD_C7") (pintype "passive"))
      (node (ref "U36") (pin "C8") (pinfunction "VDD_C8") (pintype "passive"))
      (node (ref "U36") (pin "C9") (pinfunction "VDD_C9") (pintype "passive"))
      (node (ref "U36") (pin "F3") (pinfunction "VDD_F3") (pintype "passive"))
      (node (ref "U36") (pin "G13") (pinfunction "VDD_G13") (pintype "passive"))
      (node (ref "U36") (pin "G3") (pinfunction "VDD_G3") (pintype "passive"))
      (node (ref "U36") (pin "H13") (pinfunction "VDD_H13") (pintype "passive"))
      (node (ref "U36") (pin "J12") (pinfunction "VDD_J12") (pintype "passive"))
      (node (ref "U36") (pin "J13") (pinfunction "VDD_J13") (pintype "passive"))
      (node (ref "U36") (pin "K4") (pinfunction "VDD_K4") (pintype "passive"))
      (node (ref "U36") (pin "N10") (pinfunction "VDD_N10") (pintype "passive"))
      (node (ref "U36") (pin "N8") (pinfunction "VDD_N8") (pintype "passive"))
      (node (ref "U36") (pin "N9") (pinfunction "VDD_N9") (pintype "passive"))
      (node (ref "U36") (pin "P1") (pinfunction "VREF+_P1") (pintype "passive"))
      (node (ref "U36") (pin "R1") (pinfunction "VDDA_R1") (pintype "passive"))
    )
    (net (code "37") (name "5V_STLK") (class "Default")
      (node (ref "C165") (pin "2") (pinfunction "2_2") (pintype "passive"))
      (node (ref "C169") (pin "2") (pinfunction "2_2") (pintype "passive"))
      (node (ref "R216") (pin "2") (pinfunction "2_2") (pintype "passive"))
      (node (ref "R230") (pin "1") (pinfunction "1_1") (pintype "passive"))
      (node (ref "U49") (pin "1") (pinfunction "OUT_1") (pintype "passive"))
      (node (ref "U52") (pin "5") (pinfunction "OUT_5") (pintype "passive"))
      (node (ref "U52") (pin "6") (pinfunction "QOD_6") (pintype "passive"))
    )
    (net (code "38") (name "GND") (class "Default")
      (node (ref "C110") (pin "1") (pinfunction "1_1") (pintype "passive"))
      (node (ref "C129") (pin "1") (pinfunction "1_1") (pintype "passive"))
      (node (ref "C131") (pin "1") (pinfunction "1_1") (pintype "passive"))
      (node (ref "C132") (pin "1") (pinfunction "1_1") (pintype "passive"))
      (node (ref "C133") (pin "1") (pinfunction "1_1") (pintype "passive"))
      (node (ref "C140") (pin "2") (pinfunction "2_2") (pintype "passive"))
      (node (ref "C145") (pin "1") (pinfunction "1_1") (pintype "passive"))
      (node (ref "C149") (pin "1") (pinfunction "1_1") (pintype "passive"))
      (node (ref "C157") (pin "2") (pinfunction "2_2") (pintype "passive"))
      (node (ref "C158") (pin "2") (pinfunction "2_2") (pintype "passive"))
      (node (ref "C160") (pin "1") (pinfunction "1_1") (pintype "passive"))
      (node (ref "C164") (pin "2") (pinfunction "2_2") (pintype "passive"))
      (node (ref "C165") (pin "1") (pinfunction "1_1") (pintype "passive"))
      (node (ref "C166") (pin "1") (pinfunction "1_1") (pintype "passive"))
      (node (ref "C169") (pin "1") (pinfunction "1_1") (pintype "passive"))
      (node (ref "C172") (pin "1") (pinfunction "1_1") (pintype "passive"))
      (node (ref "C173") (pin "1") (pinfunction "1_1") (pintype "passive"))
      (node (ref "C25") (pin "1") (pinfunction "1_1") (pintype "passive"))
      (node (ref "C281") (pin "2") (pinfunction "2_2") (pintype "passive"))
      (node (ref "C282") (pin "2") (pinfunction "2_2") (pintype "passive"))
      (node (ref "C289") (pin "2") (pinfunction "2_2") (pintype "passive"))
      (node (ref "C290") (pin "2") (pinfunction "2_2") (pintype "passive"))
      (node (ref "C297") (pin "2") (pinfunction "2_2") (pintype "passive"))
      (node (ref "C298") (pin "2") (pinfunction "2_2") (pintype "passive"))
      (node (ref "C299") (pin "2") (pinfunction "2_2") (pintype "passive"))
      (node (ref "C303") (pin "2") (pinfunction "2_2") (pintype "passive"))
      (node (ref "C310") (pin "2") (pinfunction "2_2") (pintype "passive"))
      (node (ref "C311") (pin "2") (pinfunction "2_2") (pintype "passive"))
      (node (ref "C324") (pin "2") (pinfunction "2_2") (pintype "passive"))
      (node (ref "C325") (pin "2") (pinfunction "2_2") (pintype "passive"))
      (node (ref "C326") (pin "2") (pinfunction "2_2") (pintype "passive"))
      (node (ref "C327") (pin "2") (pinfunction "2_2") (pintype "passive"))
      (node (ref "C328") (pin "2") (pinfunction "2_2") (pintype "passive"))
      (node (ref "C329") (pin "2") (pinfunction "2_2") (pintype "passive"))
      (node (ref "C333") (pin "2") (pinfunction "2_2") (pintype "passive"))
      (node (ref "CN14") (pin "3") (pinfunction "3_3") (pintype "passive"))
      (node (ref "CN21") (pin "A1") (pinfunction "GND1_A1") (pintype "passive"))
      (node (ref "CN21") (pin "A12") (pinfunction "GND2_A12") (pintype "passive"))
      (node (ref "CN21") (pin "B1") (pinfunction "GND3_B1") (pintype "passive"))
      (node (ref "CN21") (pin "B12") (pinfunction "GND4_B12") (pintype "passive"))
      (node (ref "CN21") (pin "SH1") (pinfunction "Shield1_SH1") (pintype "passive"))
      (node (ref "CN21") (pin "SH2") (pinfunction "Shield2_SH2") (pintype "passive"))
      (node (ref "CN21") (pin "SH3") (pinfunction "Shield3_SH3") (pintype "passive"))
      (node (ref "CN21") (pin "SH4") (pinfunction "Shield4_SH4") (pintype "passive"))
      (node (ref "JP3") (pin "2") (pinfunction "NO_2") (pintype "passive"))
      (node (ref "LD5") (pin "3") (pinfunction "RED_cathode_3") (pintype "passive"))
      (node (ref "LD6") (pin "3") (pinfunction "RED_cathode_3") (pintype "passive"))
      (node (ref "R194") (pin "2") (pinfunction "2_2") (pintype "passive"))
      (node (ref "R213") (pin "2") (pinfunction "2_2") (pintype "passive"))
      (node (ref "R215") (pin "2") (pinfunction "2_2") (pintype "passive"))
      (node (ref "R221") (pin "2") (pinfunction "2_2") (pintype "passive"))
      (node (ref "R222") (pin "2") (pinfunction "2_2") (pintype "passive"))
      (node (ref "R226") (pin "1") (pinfunction "1_1") (pintype "passive"))
      (node (ref "R229") (pin "1") (pinfunction "1_1") (pintype "passive"))
      (node (ref "R239") (pin "1") (pinfunction "1_1") (pintype "passive"))
      (node (ref "R242") (pin "2") (pinfunction "2_2") (pintype "passive"))
      (node (ref "U35") (pin "2") (pinfunction "GND_2") (pintype "passive"))
      (node (ref "U36") (pin "D5") (pinfunction "VSS_D5") (pintype "passive"))
      (node (ref "U36") (pin "D6") (pinfunction "BOOT0_D6") (pintype "passive"))
      (node (ref "U36") (pin "D7") (pinfunction "VSS_D7") (pintype "passive"))
      (node (ref "U36") (pin "D8") (pinfunction "VSS_D8") (pintype "passive"))
      (node (ref "U36") (pin "D9") (pinfunction "VSS_D9") (pintype "passive"))
      (node (ref "U36") (pin "F10") (pinfunction "VSS_F10") (pintype "passive"))
      (node (ref "U36") (pin "F12") (pinfunction "VSS_F12") (pintype "passive"))
      (node (ref "U36") (pin "F2") (pinfunction "VSS_F2") (pintype "passive"))
      (node (ref "U36") (pin "F6") (pinfunction "VSS_F6") (pintype "passive"))
      (node (ref "U36") (pin "F7") (pinfunction "VSS_F7") (pintype "passive"))
      (node (ref "U36") (pin "F8") (pinfunction "VSS_F8") (pintype "passive"))
      (node (ref "U36") (pin "F9") (pinfunction "VSS_F9") (pintype "passive"))
      (node (ref "U36") (pin "G10") (pinfunction "VSS_G10") (pintype "passive"))
      (node (ref "U36") (pin "G12") (pinfunction "VSS_G12") (pintype "passive"))
      (node (ref "U36") (pin "G2") (pinfunction "VSS_G2") (pintype "passive"))
      (node (ref "U36") (pin "G6") (pinfunction "VSS_G6") (pintype "passive"))
      (node (ref "U36") (pin "G7") (pinfunction "VSS_G7") (pintype "passive"))
      (node (ref "U36") (pin "G8") (pinfunction "VSS_G8") (pintype "passive"))
      (node (ref "U36") (pin "G9") (pinfunction "VSS_G9") (pintype "passive"))
      (node (ref "U36") (pin "H10") (pinfunction "VSS_H10") (pintype "passive"))
      (node (ref "U36") (pin "H12") (pinfunction "VSS_H12") (pintype "passive"))
      (node (ref "U36") (pin "H6") (pinfunction "VSS_H6") (pintype "passive"))
      (node (ref "U36") (pin "H7") (pinfunction "VSS_H7") (pintype "passive"))
      (node (ref "U36") (pin "H8") (pinfunction "VSS_H8") (pintype "passive"))
      (node (ref "U36") (pin "H9") (pinfunction "VSS_H9") (pintype "passive"))
      (node (ref "U36") (pin "J10") (pinfunction "VSS_J10") (pintype "passive"))
      (node (ref "U36") (pin "J6") (pinfunction "VSS_J6") (pintype "passive"))
      (node (ref "U36") (pin "J7") (pinfunction "VSS_J7") (pintype "passive"))
      (node (ref "U36") (pin "J8") (pinfunction "VSS_J8") (pintype "passive"))
      (node (ref "U36") (pin "J9") (pinfunction "VSS_J9") (pintype "passive"))
      (node (ref "U36") (pin "K10") (pinfunction "VSS_K10") (pintype "passive"))
      (node (ref "U36") (pin "K6") (pinfunction "VSS_K6") (pintype "passive"))
      (node (ref "U36") (pin "K7") (pinfunction "VSS_K7") (pintype "passive"))
      (node (ref "U36") (pin "K8") (pinfunction "VSS_K8") (pintype "passive"))
      (node (ref "U36") (pin "K9") (pinfunction "VSS_K9") (pintype "passive"))
      (node (ref "U36") (pin "L4") (pinfunction "BYPASS-REG_L4") (pintype "passive"))
      (node (ref "U36") (pin "M1") (pinfunction "VSSA_M1") (pintype "passive"))
      (node (ref "U36") (pin "M8") (pinfunction "VSS_M8") (pintype "passive"))
      (node (ref "U36") (pin "M9") (pinfunction "VSS_M9") (pintype "passive"))
      (node (ref "U36") (pin "N1") (pinfunction "VREF-_N1") (pintype "passive"))
      (node (ref "U47") (pin "3") (pinfunction "GND_3") (pintype "passive"))
      (node (ref "U47") (pin "4") (pinfunction "GND_4") (pintype "passive"))
      (node (ref "U48") (pin "2") (pinfunction "GND_2") (pintype "passive"))
      (node (ref "U49") (pin "2") (pinfunction "GND_2") (pintype "passive"))
      (node (ref "U52") (pin "8") (pinfunction "GND_8") (pintype "passive"))
      (node (ref "U52") (pin "9") (pinfunction "EP_9") (pintype "passive"))
      (node (ref "X7") (pin "2") (pinfunction "2_2") (pintype "passive"))
      (node (ref "X7") (pin "4") (pinfunction "4_4") (pintype "passive"))
    )
    (net (code "39") (name "Net-(C131-Pad2)") (class "Default")
      (node (ref "C131") (pin "2") (pinfunction "2_2") (pintype "passive"))
      (node (ref "R181") (pin "2") (pinfunction "2_2") (pintype "passive"))
      (node (ref "TP33") (pin "1") (pinfunction "1_1") (pintype "passive"))
    )
    (net (code "40") (name "Net-(CN21-CC1)") (class "Default")
      (node (ref "CN21") (pin "A5") (pinfunction "CC1_A5") (pintype "passive"))
      (node (ref "R217") (pin "2") (pinfunction "2_2") (pintype "passive"))
      (node (ref "R221") (pin "1") (pinfunction "1_1") (pintype "passive"))
    )
    (net (code "41") (name "Net-(CN21-CC2)") (class "Default")
      (node (ref "CN21") (pin "B5") (pinfunction "CC2_B5") (pintype "passive"))
      (node (ref "R218") (pin "2") (pinfunction "2_2") (pintype "passive"))
      (node (ref "R222") (pin "1") (pinfunction "1_1") (pintype "passive"))
    )
    (net (code "42") (name "Net-(LD5-Green_cathode)") (class "Default")
      (node (ref "LD5") (pin "2") (pinfunction "Green_cathode_2") (pintype "passive"))
      (node (ref "R130") (pin "2") (pinfunction "2_2") (pintype "passive"))
    )
    (net (code "43") (name "Net-(LD5-Red_anode)") (class "Default")
      (node (ref "LD5") (pin "1") (pinfunction "Red_anode_1") (pintype "passive"))
      (node (ref "R131") (pin "1") (pinfunction "1_1") (pintype "passive"))
    )
    (net (code "44") (name "Net-(LD6-Green_cathode)") (class "Default")
      (node (ref "LD6") (pin "2") (pinfunction "Green_cathode_2") (pintype "passive"))
      (node (ref "R132") (pin "1") (pinfunction "1_1") (pintype "passive"))
    )
    (net (code "45") (name "Net-(LD6-Red_anode)") (class "Default")
      (node (ref "LD6") (pin "1") (pinfunction "Red_anode_1") (pintype "passive"))
      (node (ref "R133") (pin "1") (pinfunction "1_1") (pintype "passive"))
    )
    (net (code "46") (name "Net-(U36A-HW_TYP_0{slash}PI4)") (class "Default")
      (node (ref "R156") (pin "1") (pinfunction "1_1") (pintype "passive"))
      (node (ref "U36") (pin "C4") (pinfunction "HW_TYP_1/PI5_C4") (pintype "passive"))
      (node (ref "U36") (pin "D4") (pinfunction "HW_TYP_0/PI4_D4") (pintype "passive"))
    )
    (net (code "47") (name "Net-(U36A-REXT_OTGPHY)") (class "Default")
      (node (ref "R194") (pin "1") (pinfunction "1_1") (pintype "passive"))
      (node (ref "U36") (pin "J15") (pinfunction "REXT_OTGPHY_J15") (pintype "passive"))
    )
    (net (code "48") (name "Net-(U36A-T_MCO{slash}PA8)") (class "Default")
      (node (ref "R181") (pin "1") (pinfunction "1_1") (pintype "passive"))
      (node (ref "U36") (pin "F15") (pinfunction "T_MCO/PA8_F15") (pintype "passive"))
    )
    (net (code "49") (name "Net-(U36A-T_NRST{slash}PA6)") (class "Default")
      (node (ref "R212") (pin "1") (pinfunction "1_1") (pintype "passive"))
      (node (ref "U36") (pin "P3") (pinfunction "T_NRST/PA6_P3") (pintype "passive"))
    )
    (net (code "50") (name "Net-(U36A-V12_OTGPHY)") (class "Default")
      (node (ref "C145") (pin "2") (pinfunction "2_2") (pintype "passive"))
      (node (ref "U36") (pin "J14") (pinfunction "V12_OTGPHY_J14") (pintype "passive"))
    )
    (net (code "51") (name "Net-(U36B-VCAP1)") (class "Default")
      (node (ref "C160") (pin "2") (pinfunction "2_2") (pintype "passive"))
      (node (ref "U36") (pin "M10") (pinfunction "VCAP1_M10") (pintype "passive"))
    )
    (net (code "52") (name "Net-(U36B-VCAP2)") (class "Default")
      (node (ref "C132") (pin "2") (pinfunction "2_2") (pintype "passive"))
      (node (ref "U36") (pin "F13") (pinfunction "VCAP2_F13") (pintype "passive"))
    )
    (net (code "53") (name "Net-(U36C-GPIO0{slash}PE2)") (class "Default")
      (node (ref "TP29") (pin "1") (pinfunction "1_1") (pintype "passive"))
      (node (ref "U36") (pin "A2") (pinfunction "GPIO0/PE2_A2") (pintype "passive"))
    )
    (net (code "54") (name "Net-(U36C-GPIO1{slash}PE4)") (class "Default")
      (node (ref "TP28") (pin "1") (pinfunction "1_1") (pintype "passive"))
      (node (ref "U36") (pin "B1") (pinfunction "GPIO1/PE4_B1") (pintype "passive"))
    )
    (net (code "55") (name "Net-(U36C-GPIO2{slash}PE5)") (class "Default")
      (node (ref "TP26") (pin "1") (pinfunction "1_1") (pintype "passive"))
      (node (ref "U36") (pin "B2") (pinfunction "GPIO2/PE5_B2") (pintype "passive"))
    )
    (net (code "56") (name "Net-(U36C-GPIO3{slash}PE6)") (class "Default")
      (node (ref "TP27") (pin "1") (pinfunction "1_1") (pintype "passive"))
      (node (ref "U36") (pin "B3") (pinfunction "GPIO3/PE6_B3") (pintype "passive"))
    )
    (net (code "57") (name "Net-(U36C-UART_RX{slash}PB11)") (class "Default")
      (node (ref "R211") (pin "2") (pinfunction "2_2") (pintype "passive"))
      (node (ref "U36") (pin "R13") (pinfunction "UART_RX/PB11_R13") (pintype "passive"))
    )
    (net (code "58") (name "Net-(U36C-UART_TX{slash}PC10)") (class "Default")
      (node (ref "R155") (pin "2") (pinfunction "2_2") (pintype "passive"))
      (node (ref "U36") (pin "B14") (pinfunction "UART_TX/PC10_B14") (pintype "passive"))
    )
    (net (code "59") (name "Net-(U52-ILM)") (class "Default")
      (node (ref "R240") (pin "1") (pinfunction "1_1") (pintype "passive"))
      (node (ref "R241") (pin "1") (pinfunction "1_1") (pintype "passive"))
      (node (ref "R242") (pin "1") (pinfunction "1_1") (pintype "passive"))
      (node (ref "U52") (pin "7") (pinfunction "ILM_7") (pintype "passive"))
    )
    (net (code "60") (name "Net-(U52-dVdt)") (class "Default")
      (node (ref "C173") (pin "2") (pinfunction "2_2") (pintype "passive"))
      (node (ref "U52") (pin "1") (pinfunction "dVdt_1") (pintype "passive"))
    )
    (net (code "61") (name "VBUS_STLK") (class "Default")
      (node (ref "C110") (pin "2") (pinfunction "2_2") (pintype "passive"))
      (node (ref "C164") (pin "1") (pinfunction "1_1") (pintype "passive"))
      (node (ref "C166") (pin "2") (pinfunction "2_2") (pintype "passive"))
      (node (ref "C172") (pin "2") (pinfunction "2_2") (pintype "passive"))
      (node (ref "CN21") (pin "A4") (pinfunction "VBUS1_A4") (pintype "passive"))
      (node (ref "CN21") (pin "A9") (pinfunction "VBUS2_A9") (pintype "passive"))
      (node (ref "CN21") (pin "B4") (pinfunction "VBUS3_B4") (pintype "passive"))
      (node (ref "CN21") (pin "B9") (pinfunction "VBUS4_B9") (pintype "passive"))
      (node (ref "U35") (pin "3") (pinfunction "VIN_3") (pintype "passive"))
      (node (ref "U35") (pin "5") (pinfunction "EN_5") (pintype "passive"))
      (node (ref "U48") (pin "1") (pinfunction "IO1_1") (pintype "passive"))
      (node (ref "U49") (pin "5") (pinfunction "IN_5") (pintype "passive"))
      (node (ref "U52") (pin "3") (pinfunction "IN_3") (pintype "passive"))
      (node (ref "U52") (pin "4") (pinfunction "IN_4") (pintype "passive"))
    )
    (net (code "62") (name "VDDIO") (class "Default")
      (node (ref "LNK13") (pin "1") (pinfunction "1_1") (pintype "passive"))
    )
    (net (code "63") (name "unconnected-(CN21-RX1+-PadB11)") (class "Default")
      (node (ref "CN21") (pin "B11") (pinfunction "RX1+_B11") (pintype "passive+no_connect"))
    )
    (net (code "64") (name "unconnected-(CN21-RX1--PadB10)") (class "Default")
      (node (ref "CN21") (pin "B10") (pinfunction "RX1-_B10") (pintype "passive+no_connect"))
    )
    (net (code "65") (name "unconnected-(CN21-RX2+-PadA11)") (class "Default")
      (node (ref "CN21") (pin "A11") (pinfunction "RX2+_A11") (pintype "passive+no_connect"))
    )
    (net (code "66") (name "unconnected-(CN21-RX2--PadA10)") (class "Default")
      (node (ref "CN21") (pin "A10") (pinfunction "RX2-_A10") (pintype "passive+no_connect"))
    )
    (net (code "67") (name "unconnected-(CN21-SBU1-PadA8)") (class "Default")
      (node (ref "CN21") (pin "A8") (pinfunction "SBU1_A8") (pintype "passive+no_connect"))
    )
    (net (code "68") (name "unconnected-(CN21-SBU2-PadB8)") (class "Default")
      (node (ref "CN21") (pin "B8") (pinfunction "SBU2_B8") (pintype "passive+no_connect"))
    )
    (net (code "69") (name "unconnected-(CN21-TX1+-PadA2)") (class "Default")
      (node (ref "CN21") (pin "A2") (pinfunction "TX1+_A2") (pintype "passive+no_connect"))
    )
    (net (code "70") (name "unconnected-(CN21-TX1--PadA3)") (class "Default")
      (node (ref "CN21") (pin "A3") (pinfunction "TX1-_A3") (pintype "passive+no_connect"))
    )
    (net (code "71") (name "unconnected-(CN21-TX2+-PadB2)") (class "Default")
      (node (ref "CN21") (pin "B2") (pinfunction "TX2+_B2") (pintype "passive+no_connect"))
    )
    (net (code "72") (name "unconnected-(CN21-TX2--PadB3)") (class "Default")
      (node (ref "CN21") (pin "B3") (pinfunction "TX2-_B3") (pintype "passive+no_connect"))
    )
    (net (code "73") (name "unconnected-(U35-NC{slash}ADJ-Pad4)") (class "Default")
      (node (ref "U35") (pin "4") (pinfunction "NC/ADJ_4") (pintype "passive+no_connect"))
    )
    (net (code "74") (name "unconnected-(U36A-GNDDetect{slash}PG5-PadK13)") (class "Default")
      (node (ref "U36") (pin "K13") (pinfunction "GNDDetect/PG5_K13") (pintype "passive+no_connect"))
    )
    (net (code "75") (name "unconnected-(U36A-T_JNRST{slash}PF13-PadN6)") (class "Default")
      (node (ref "U36") (pin "N6") (pinfunction "T_JNRST/PF13_N6") (pintype "passive+no_connect"))
    )
    (net (code "76") (name "unconnected-(U36A-T_SW_DIR{slash}PA7-PadR3)") (class "Default")
      (node (ref "U36") (pin "R3") (pinfunction "T_SW_DIR/PA7_R3") (pintype "passive+no_connect"))
    )
    (net (code "77") (name "unconnected-(U36C-CAN_RX{slash}PA11-PadC15)") (class "Default")
      (node (ref "U36") (pin "C15") (pinfunction "CAN_RX/PA11_C15") (pintype "passive+no_connect"))
    )
    (net (code "78") (name "unconnected-(U36C-CAN_TX{slash}PA12-PadB15)") (class "Default")
      (node (ref "U36") (pin "B15") (pinfunction "CAN_TX/PA12_B15") (pintype "passive+no_connect"))
    )
    (net (code "79") (name "unconnected-(U36C-I2C_SCL{slash}PB8-PadA5)") (class "Default")
      (node (ref "U36") (pin "A5") (pinfunction "I2C_SCL/PB8_A5") (pintype "passive+no_connect"))
    )
    (net (code "80") (name "unconnected-(U36C-I2C_SDA{slash}PB9-PadB4)") (class "Default")
      (node (ref "U36") (pin "B4") (pinfunction "I2C_SDA/PB9_B4") (pintype "passive+no_connect"))
    )
    (net (code "81") (name "unconnected-(U36C-SPI_MISO{slash}PC2-PadM4)") (class "Default")
      (node (ref "U36") (pin "M4") (pinfunction "SPI_MISO/PC2_M4") (pintype "passive+no_connect"))
    )
    (net (code "82") (name "unconnected-(U36C-SPI_MOSI{slash}PC1-PadM3)") (class "Default")
      (node (ref "U36") (pin "M3") (pinfunction "SPI_MOSI/PC1_M3") (pintype "passive+no_connect"))
    )
    (net (code "83") (name "unconnected-(U36C-SPI_NSS{slash}PB4-PadA9)") (class "Default")
      (node (ref "U36") (pin "A9") (pinfunction "SPI_NSS/PB4_A9") (pintype "passive+no_connect"))
    )
    (net (code "84") (name "unconnected-(U36C-SPI_SCK{slash}PA9-PadE15)") (class "Default")
      (node (ref "U36") (pin "E15") (pinfunction "SPI_SCK/PA9_E15") (pintype "passive+no_connect"))
    )
    (net (code "85") (name "unconnected-(U36C-UART_CTS{slash}PD11-PadN14)") (class "Default")
      (node (ref "U36") (pin "N14") (pinfunction "UART_CTS/PD11_N14") (pintype "passive+no_connect"))
    )
    (net (code "86") (name "unconnected-(U36C-UART_RTS{slash}PD12-PadN13)") (class "Default")
      (node (ref "U36") (pin "N13") (pinfunction "UART_RTS/PD12_N13") (pintype "passive+no_connect"))
    )
  )
)
